# BleSensorC.net
KiCad netlist of a schematic drawn in EAGLE
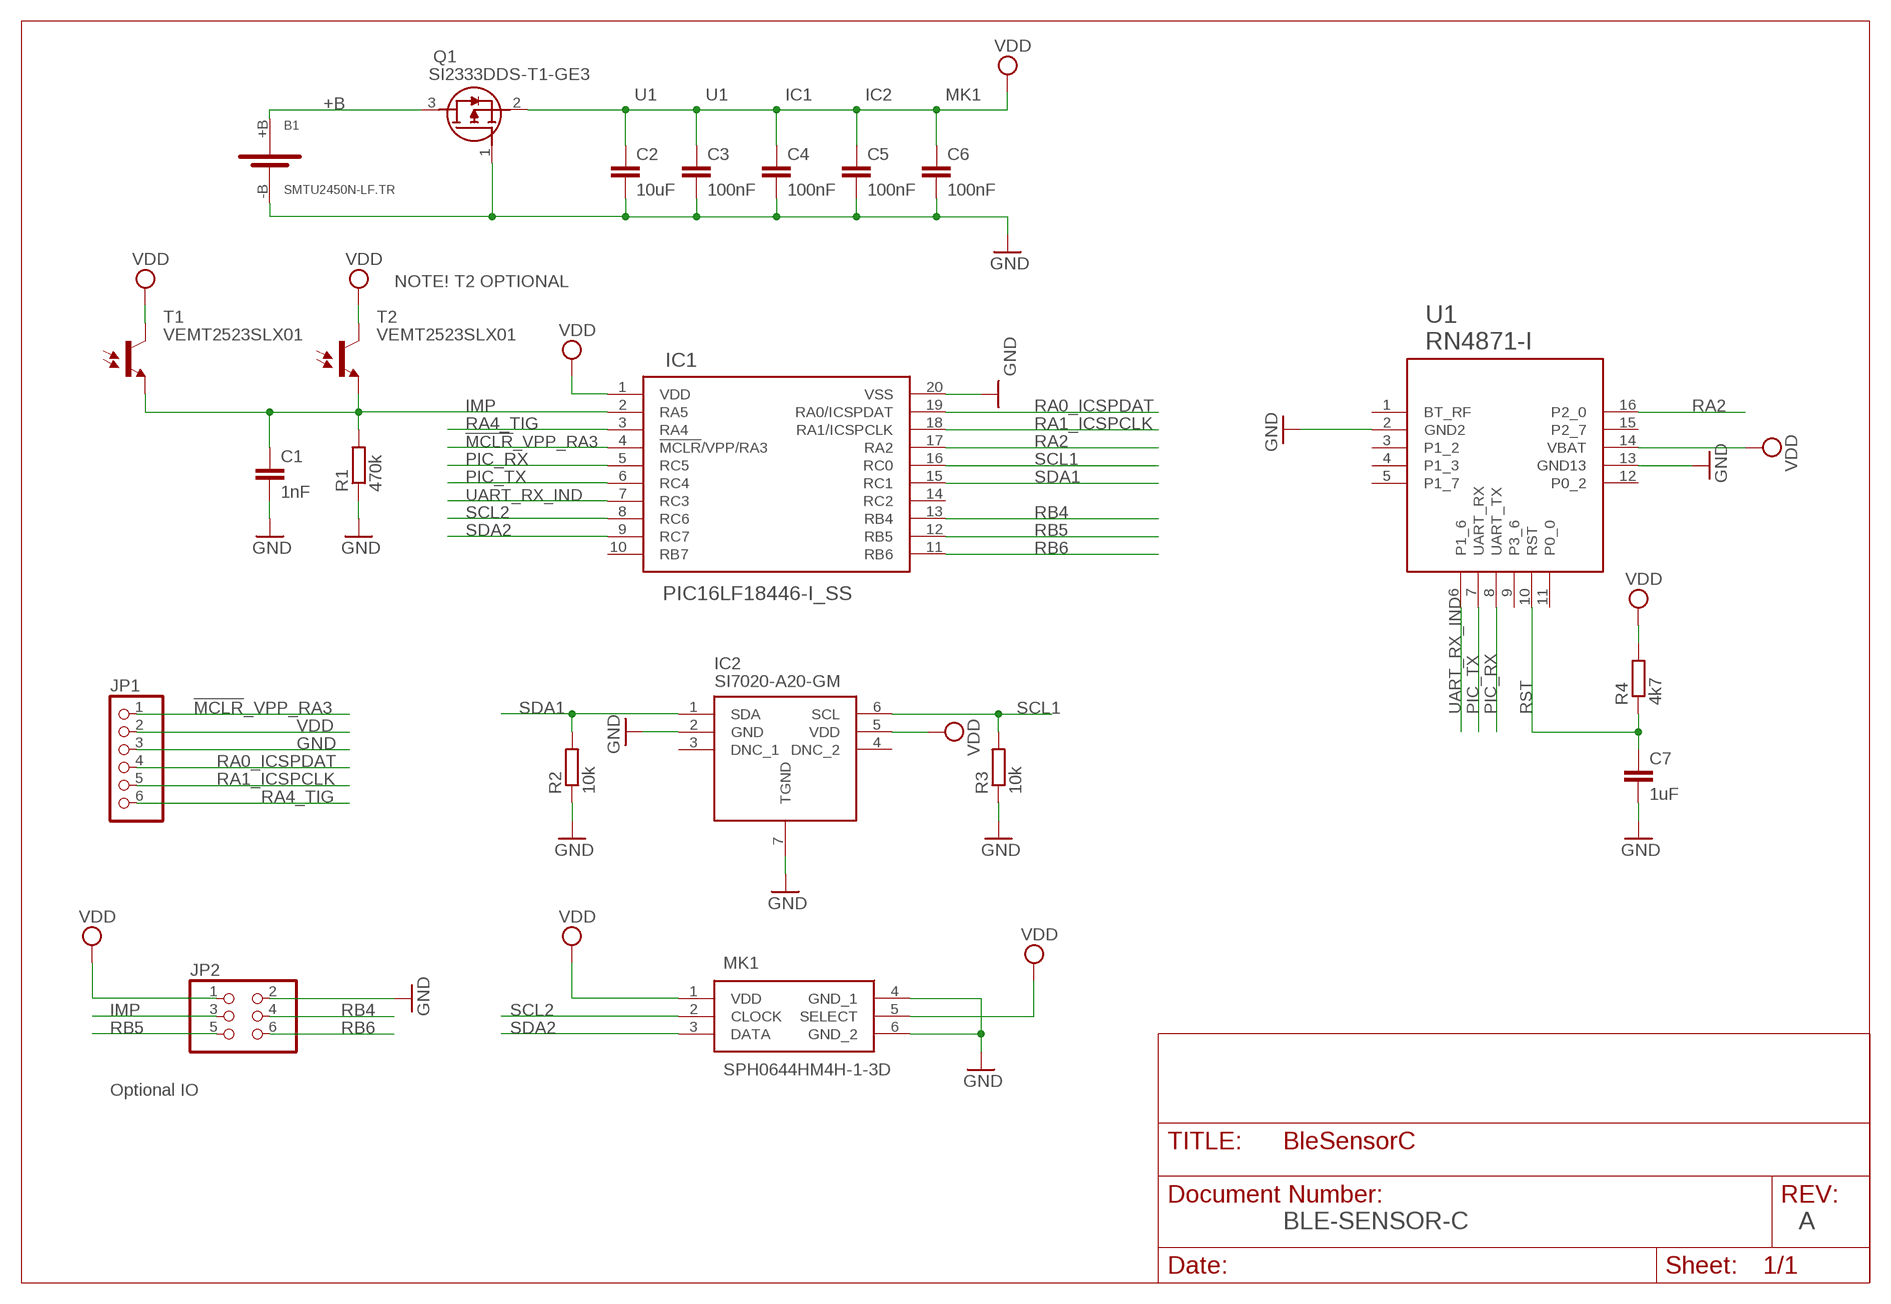
[diagram p0: schematic, sheet 1]

(export (version "E")
  (design (tool "Eeschema 10.0.6"))
  (components
    (comp (ref "B1")
      (value "SMTU2450N-LF.TR")
      (footprint "eagle-import:SMTU2450N-LF")
      (libsource (lib "eagle-import") (part "SMTU2450N-LF.TR"))
    )
    (comp (ref "C1")
      (value "1nF")
      (footprint "eagle-import:C0805")
      (libsource (lib "eagle-import") (part "C-EUC0805"))
    )
    (comp (ref "C2")
      (value "10uF")
      (footprint "eagle-import:C0805")
      (libsource (lib "eagle-import") (part "C-EUC0805"))
    )
    (comp (ref "C3")
      (value "100nF")
      (footprint "eagle-import:C0805")
      (libsource (lib "eagle-import") (part "C-EUC0805"))
    )
    (comp (ref "C4")
      (value "100nF")
      (footprint "eagle-import:C0805")
      (libsource (lib "eagle-import") (part "C-EUC0805"))
    )
    (comp (ref "C5")
      (value "100nF")
      (footprint "eagle-import:C0805")
      (libsource (lib "eagle-import") (part "C-EUC0805"))
    )
    (comp (ref "C6")
      (value "100nF")
      (footprint "eagle-import:C0805")
      (libsource (lib "eagle-import") (part "C-EUC0805"))
    )
    (comp (ref "C7")
      (value "1uF")
      (footprint "eagle-import:C0805")
      (libsource (lib "eagle-import") (part "C-EUC0805"))
    )
    (comp (ref "IC1")
      (value "PIC16LF18446-I_SS")
      (footprint "eagle-import:SOP65P780X200-20")
      (fields (field (name "MANUFACTURER_PART_NUMBER") "PIC16LF18446-I/SS"))
      (libsource (lib "eagle-import") (part "PIC16LF18446-I_SS"))
    )
    (comp (ref "IC2")
      (value "SI7020-A20-GM")
      (footprint "eagle-import:DFN-6-3X3-SI7020")
      (fields
        (field (name "MANUFACTURER_PART_NUMBER") "Si7020-A20-GM")
        (field (name "MOUSER_PART_NUMBER") "634-SI7020-A20-GM")
      )
      (libsource (lib "eagle-import") (part "SI7020-A20-GM"))
    )
    (comp (ref "JP1")
      (value "PINHD-1X6-S")
      (footprint "eagle-import:1X06-S")
      (libsource (lib "eagle-import") (part "PINHD-1X6-S"))
    )
    (comp (ref "JP2")
      (value "PINHD-2X3")
      (footprint "eagle-import:2X03")
      (libsource (lib "eagle-import") (part "PINHD-2X3"))
    )
    (comp (ref "MK1")
      (value "SPH0644HM4H-1-3D")
      (footprint "eagle-import:SOJ88P324X95-6")
      (libsource (lib "eagle-import") (part "SPH0644HM4H-1-3D"))
    )
    (comp (ref "Q1")
      (value "SI2333DDS-T1-GE3")
      (footprint "eagle-import:SOT95P237X112-3")
      (fields (field (name "MOUSER_PART_NUMBER") "78-SI2333DDS-T1-GE3"))
      (libsource (lib "eagle-import") (part "SI2333DDS-T1-GE3"))
    )
    (comp (ref "R1")
      (value "470k")
      (footprint "eagle-import:R0805")
      (libsource (lib "eagle-import") (part "R-EU_R0805"))
    )
    (comp (ref "R2")
      (value "10k")
      (footprint "eagle-import:R0805")
      (libsource (lib "eagle-import") (part "R-EU_R0805"))
    )
    (comp (ref "R3")
      (value "10k")
      (footprint "eagle-import:R0805")
      (libsource (lib "eagle-import") (part "R-EU_R0805"))
    )
    (comp (ref "R4")
      (value "4k7")
      (footprint "eagle-import:R0805")
      (libsource (lib "eagle-import") (part "R-EU_R0805"))
    )
    (comp (ref "T1")
      (value "VEMT2523SLX01")
      (footprint "eagle-import:VEMT2523SL")
      (libsource (lib "eagle-import") (part "VEMT2523SLX01"))
    )
    (comp (ref "T2")
      (value "VEMT2523SLX01")
      (footprint "eagle-import:VEMT2523SL")
      (libsource (lib "eagle-import") (part "VEMT2523SLX01"))
    )
    (comp (ref "U1")
      (value "RN4871-I")
      (footprint "eagle-import:RN4871")
      (fields (field (name "MPN") "RN4871-I/RM130"))
      (libsource (lib "eagle-import") (part "RN4871-I"))
    )
  )
  (nets
    (net (code "1") (name "/+B") (class "Default")
      (node (ref "B1") (pin "+B") (pinfunction "+B_+B") (pintype "power_in"))
      (node (ref "Q1") (pin "3") (pinfunction "D_3") (pintype "bidirectional"))
    )
    (net (code "2") (name "/IMP") (class "Default")
      (node (ref "C1") (pin "1") (pinfunction "1_1") (pintype "passive"))
      (node (ref "IC1") (pin "2") (pinfunction "RA5_2") (pintype "bidirectional"))
      (node (ref "JP2") (pin "3") (pinfunction "3_3") (pintype "passive"))
      (node (ref "R1") (pin "2") (pinfunction "2_2") (pintype "passive"))
      (node (ref "T1") (pin "E") (pinfunction "E_E") (pintype "passive"))
      (node (ref "T2") (pin "E") (pinfunction "E_E") (pintype "passive"))
    )
    (net (code "3") (name "/PIC_RX") (class "Default")
      (node (ref "IC1") (pin "5") (pinfunction "RC5_5") (pintype "bidirectional"))
      (node (ref "U1") (pin "8") (pinfunction "UART_TX_8") (pintype "bidirectional"))
    )
    (net (code "4") (name "/PIC_TX") (class "Default")
      (node (ref "IC1") (pin "6") (pinfunction "RC4_6") (pintype "bidirectional"))
      (node (ref "U1") (pin "7") (pinfunction "UART_RX_7") (pintype "bidirectional"))
    )
    (net (code "5") (name "/RA0_ICSPDAT") (class "Default")
      (node (ref "IC1") (pin "19") (pinfunction "RA0/ICSPDAT_19") (pintype "bidirectional"))
      (node (ref "JP1") (pin "4") (pinfunction "4_4") (pintype "passive"))
    )
    (net (code "6") (name "/RA1_ICSPCLK") (class "Default")
      (node (ref "IC1") (pin "18") (pinfunction "RA1/ICSPCLK_18") (pintype "bidirectional"))
      (node (ref "JP1") (pin "5") (pinfunction "5_5") (pintype "passive"))
    )
    (net (code "7") (name "/RA2") (class "Default")
      (node (ref "IC1") (pin "17") (pinfunction "RA2_17") (pintype "bidirectional"))
      (node (ref "U1") (pin "16") (pinfunction "P2_0_16") (pintype "bidirectional"))
    )
    (net (code "8") (name "/RA4_TIG") (class "Default")
      (node (ref "IC1") (pin "3") (pinfunction "RA4_3") (pintype "bidirectional"))
      (node (ref "JP1") (pin "6") (pinfunction "6_6") (pintype "passive"))
    )
    (net (code "9") (name "/RB4") (class "Default")
      (node (ref "IC1") (pin "13") (pinfunction "RB4_13") (pintype "bidirectional"))
      (node (ref "JP2") (pin "4") (pinfunction "4_4") (pintype "passive"))
    )
    (net (code "10") (name "/RB5") (class "Default")
      (node (ref "IC1") (pin "12") (pinfunction "RB5_12") (pintype "bidirectional"))
      (node (ref "JP2") (pin "5") (pinfunction "5_5") (pintype "passive"))
    )
    (net (code "11") (name "/RB6") (class "Default")
      (node (ref "IC1") (pin "11") (pinfunction "RB6_11") (pintype "bidirectional"))
      (node (ref "JP2") (pin "6") (pinfunction "6_6") (pintype "passive"))
    )
    (net (code "12") (name "/RST") (class "Default")
      (node (ref "C7") (pin "1") (pinfunction "1_1") (pintype "passive"))
      (node (ref "R4") (pin "1") (pinfunction "1_1") (pintype "passive"))
      (node (ref "U1") (pin "10") (pinfunction "RST_10") (pintype "bidirectional"))
    )
    (net (code "13") (name "/SCL1") (class "Default")
      (node (ref "IC1") (pin "16") (pinfunction "RC0_16") (pintype "bidirectional"))
      (node (ref "IC2") (pin "6") (pinfunction "SCL_6") (pintype "bidirectional"))
      (node (ref "R3") (pin "2") (pinfunction "2_2") (pintype "passive"))
    )
    (net (code "14") (name "/SCL2") (class "Default")
      (node (ref "IC1") (pin "8") (pinfunction "RC6_8") (pintype "bidirectional"))
      (node (ref "MK1") (pin "2") (pinfunction "CLOCK_2") (pintype "bidirectional"))
    )
    (net (code "15") (name "/SDA1") (class "Default")
      (node (ref "IC1") (pin "15") (pinfunction "RC1_15") (pintype "bidirectional"))
      (node (ref "IC2") (pin "1") (pinfunction "SDA_1") (pintype "bidirectional"))
      (node (ref "R2") (pin "2") (pinfunction "2_2") (pintype "passive"))
    )
    (net (code "16") (name "/SDA2") (class "Default")
      (node (ref "IC1") (pin "9") (pinfunction "RC7_9") (pintype "bidirectional"))
      (node (ref "MK1") (pin "3") (pinfunction "DATA_3") (pintype "bidirectional"))
    )
    (net (code "17") (name "/UART_RX_IND") (class "Default")
      (node (ref "IC1") (pin "7") (pinfunction "RC3_7") (pintype "bidirectional"))
      (node (ref "U1") (pin "6") (pinfunction "P1_6_6") (pintype "bidirectional"))
    )
    (net (code "18") (name "/~{MCLR}_VPP_RA3") (class "Default")
      (node (ref "IC1") (pin "4") (pinfunction "~{MCLR}/VPP/RA3_4") (pintype "bidirectional"))
      (node (ref "JP1") (pin "1") (pinfunction "1_1") (pintype "passive"))
    )
    (net (code "19") (name "GND") (class "Default")
      (node (ref "B1") (pin "-B") (pinfunction "-B_-B") (pintype "power_in"))
      (node (ref "C1") (pin "2") (pinfunction "2_2") (pintype "passive"))
      (node (ref "C2") (pin "2") (pinfunction "2_2") (pintype "passive"))
      (node (ref "C3") (pin "2") (pinfunction "2_2") (pintype "passive"))
      (node (ref "C4") (pin "2") (pinfunction "2_2") (pintype "passive"))
      (node (ref "C5") (pin "2") (pinfunction "2_2") (pintype "passive"))
      (node (ref "C6") (pin "2") (pinfunction "2_2") (pintype "passive"))
      (node (ref "C7") (pin "2") (pinfunction "2_2") (pintype "passive"))
      (node (ref "IC1") (pin "20") (pinfunction "VSS_20") (pintype "power_in"))
      (node (ref "IC2") (pin "2") (pinfunction "GND_2") (pintype "power_in"))
      (node (ref "IC2") (pin "7") (pinfunction "TGND_7") (pintype "power_in"))
      (node (ref "JP1") (pin "3") (pinfunction "3_3") (pintype "passive"))
      (node (ref "JP2") (pin "2") (pinfunction "2_2") (pintype "passive"))
      (node (ref "MK1") (pin "4") (pinfunction "GND_1_4") (pintype "bidirectional"))
      (node (ref "MK1") (pin "6") (pinfunction "GND_2_6") (pintype "bidirectional"))
      (node (ref "Q1") (pin "1") (pinfunction "G_1") (pintype "bidirectional"))
      (node (ref "R1") (pin "1") (pinfunction "1_1") (pintype "passive"))
      (node (ref "R2") (pin "1") (pinfunction "1_1") (pintype "passive"))
      (node (ref "R3") (pin "1") (pinfunction "1_1") (pintype "passive"))
      (node (ref "U1") (pin "13") (pinfunction "GND13_13") (pintype "power_in"))
      (node (ref "U1") (pin "2") (pinfunction "GND2_2") (pintype "power_in"))
    )
    (net (code "20") (name "VDD") (class "Default")
      (node (ref "C2") (pin "1") (pinfunction "1_1") (pintype "passive"))
      (node (ref "C3") (pin "1") (pinfunction "1_1") (pintype "passive"))
      (node (ref "C4") (pin "1") (pinfunction "1_1") (pintype "passive"))
      (node (ref "C5") (pin "1") (pinfunction "1_1") (pintype "passive"))
      (node (ref "C6") (pin "1") (pinfunction "1_1") (pintype "passive"))
      (node (ref "IC1") (pin "1") (pinfunction "VDD_1") (pintype "power_in"))
      (node (ref "IC2") (pin "5") (pinfunction "VDD_5") (pintype "power_in"))
      (node (ref "JP1") (pin "2") (pinfunction "2_2") (pintype "passive"))
      (node (ref "JP2") (pin "1") (pinfunction "1_1") (pintype "passive"))
      (node (ref "MK1") (pin "1") (pinfunction "VDD_1") (pintype "bidirectional"))
      (node (ref "MK1") (pin "5") (pinfunction "SELECT_5") (pintype "bidirectional"))
      (node (ref "Q1") (pin "2") (pinfunction "S_2") (pintype "bidirectional"))
      (node (ref "R4") (pin "2") (pinfunction "2_2") (pintype "passive"))
      (node (ref "T1") (pin "C") (pinfunction "C_C") (pintype "passive"))
      (node (ref "T2") (pin "C") (pinfunction "C_C") (pintype "passive"))
      (node (ref "U1") (pin "14") (pinfunction "VBAT_14") (pintype "power_in"))
    )
    (net (code "21") (name "unconnected-(IC1-RB7-Pad10)") (class "Default")
      (node (ref "IC1") (pin "10") (pinfunction "RB7_10") (pintype "bidirectional"))
    )
    (net (code "22") (name "unconnected-(IC1-RC2-Pad14)") (class "Default")
      (node (ref "IC1") (pin "14") (pinfunction "RC2_14") (pintype "bidirectional"))
    )
    (net (code "23") (name "unconnected-(IC2-DNC_1-Pad3)") (class "Default")
      (node (ref "IC2") (pin "3") (pinfunction "DNC_1_3") (pintype "bidirectional"))
    )
    (net (code "24") (name "unconnected-(IC2-DNC_2-Pad4)") (class "Default")
      (node (ref "IC2") (pin "4") (pinfunction "DNC_2_4") (pintype "bidirectional"))
    )
    (net (code "25") (name "unconnected-(U1-BT_RF-Pad1)") (class "Default")
      (node (ref "U1") (pin "1") (pinfunction "BT_RF_1") (pintype "bidirectional"))
    )
    (net (code "26") (name "unconnected-(U1-P0_0-Pad11)") (class "Default")
      (node (ref "U1") (pin "11") (pinfunction "P0_0_11") (pintype "bidirectional"))
    )
    (net (code "27") (name "unconnected-(U1-P0_2-Pad12)") (class "Default")
      (node (ref "U1") (pin "12") (pinfunction "P0_2_12") (pintype "bidirectional"))
    )
    (net (code "28") (name "unconnected-(U1-P1_2-Pad3)") (class "Default")
      (node (ref "U1") (pin "3") (pinfunction "P1_2_3") (pintype "bidirectional"))
    )
    (net (code "29") (name "unconnected-(U1-P1_3-Pad4)") (class "Default")
      (node (ref "U1") (pin "4") (pinfunction "P1_3_4") (pintype "bidirectional"))
    )
    (net (code "30") (name "unconnected-(U1-P1_7-Pad5)") (class "Default")
      (node (ref "U1") (pin "5") (pinfunction "P1_7_5") (pintype "bidirectional"))
    )
    (net (code "31") (name "unconnected-(U1-P2_7-Pad15)") (class "Default")
      (node (ref "U1") (pin "15") (pinfunction "P2_7_15") (pintype "bidirectional"))
    )
    (net (code "32") (name "unconnected-(U1-P3_6-Pad9)") (class "Default")
      (node (ref "U1") (pin "9") (pinfunction "P3_6_9") (pintype "bidirectional"))
    )
  )
)
